# ScreenBoard.net
KiCad netlist of a schematic drawn in Altium Designer
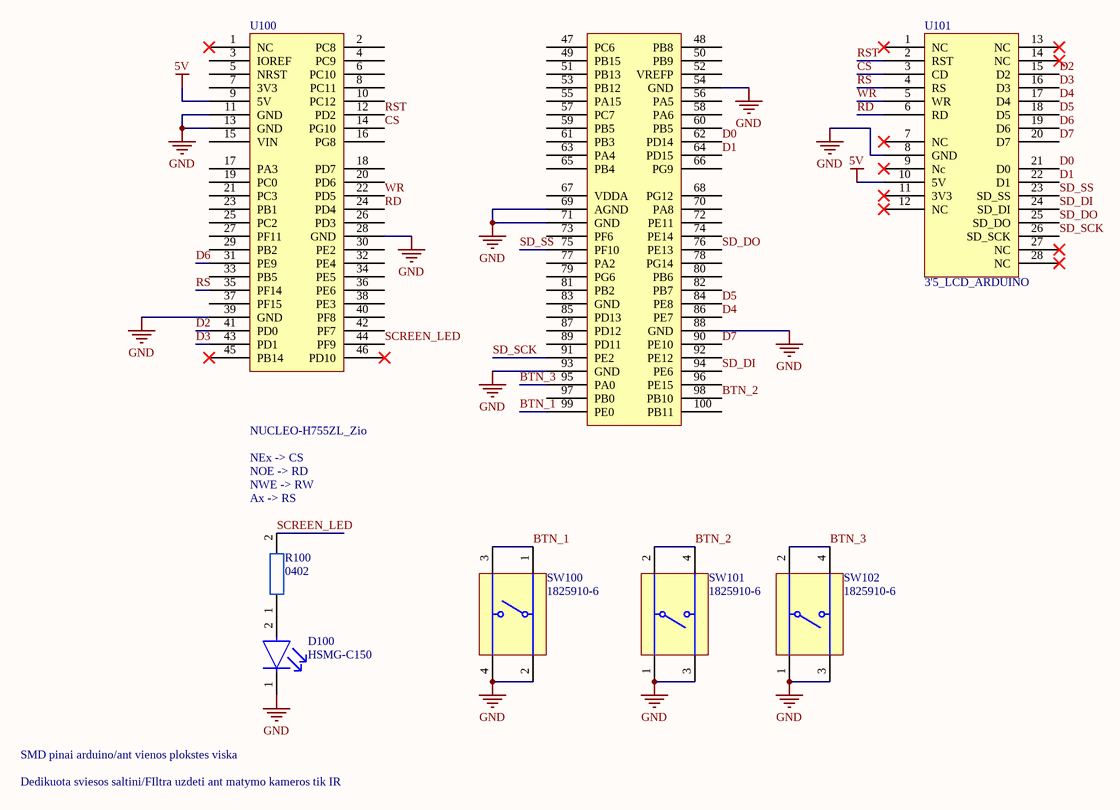
[diagram p0: ScreenBoard.SchDoc]

(export (version "E")
  (design (tool "Eeschema 10.0.6"))
  (components
    (comp (ref "D100")
      (value "HSMG-C150")
      (footprint "FP-HSMG-C150-MFG")
      (description "LED GREEN DIFFUSED 1206 SMD")
      (fields
        (field (name "MANUFACTURER") "Broadcom")
        (field (name "OCTOPART") "https://octopart.com/hsmg-c150-broadcom-71131304")
      )
      (libsource (lib "Altium Content Vault") (part "8706943c75ba83719d021d2fdc84c58"))
    )
    (comp (ref "R100")
      (value "0402")
      (footprint "0402_footprint")
      (description "0402 resistor")
      (libsource (lib "Schlib1") (part "Resistor_0402"))
    )
    (comp (ref "SW100")
      (value "1825910-6")
      (footprint "TECO-1825910-6_V")
      (description "Tact Switch, SPST-NO, 0.05 A, -35 to 85 degC, 4-Pin THD, RoHS, Bulk")
      (fields (field (name "MANUFACTURER") "TE Connectivity"))
      (libsource (lib "") (part "SW-SPST-4_A_1"))
    )
    (comp (ref "SW101")
      (value "1825910-6")
      (footprint "TECO-1825910-6_V")
      (description "Tact Switch, SPST-NO, 0.05 A, -35 to 85 degC, 4-Pin THD, RoHS, Bulk")
      (fields (field (name "MANUFACTURER") "TE Connectivity"))
      (libsource (lib "Altium Content Vault") (part "SW-SPST-4_A"))
    )
    (comp (ref "SW102")
      (value "1825910-6")
      (footprint "TECO-1825910-6_V")
      (description "Tact Switch, SPST-NO, 0.05 A, -35 to 85 degC, 4-Pin THD, RoHS, Bulk")
      (fields (field (name "MANUFACTURER") "TE Connectivity"))
      (libsource (lib "Altium Content Vault") (part "SW-SPST-4_A"))
    )
    (comp (ref "U100")
      (value "NUCLEO-H755ZL_Zio")
      (footprint "H7/H5_NUCLEO_Zio")
      (libsource (lib "Schlib1") (part "NUCLEO-H755ZL_Zio"))
    )
    (comp (ref "U101")
      (value "3'5_LCD_ARDUINO")
      (footprint "3'5_LCD_ARDUINO")
      (libsource (lib "Schlib1") (part "3'5_LCD_ARDUINO"))
    )
  )
  (nets
    (net (code "1") (name "/BTN_1") (class "Default")
      (node (ref "SW100") (pin "1") (pinfunction "1_1") (pintype "passive"))
      (node (ref "SW100") (pin "3") (pinfunction "3_3") (pintype "passive"))
      (node (ref "U100") (pin "99") (pinfunction "PE0_99") (pintype "passive"))
    )
    (net (code "2") (name "/BTN_2") (class "Default")
      (node (ref "SW101") (pin "2") (pinfunction "2_2") (pintype "passive"))
      (node (ref "SW101") (pin "4") (pinfunction "4_4") (pintype "passive"))
      (node (ref "U100") (pin "98") (pinfunction "PB10_98") (pintype "passive"))
    )
    (net (code "3") (name "/BTN_3") (class "Default")
      (node (ref "SW102") (pin "2") (pinfunction "2_2") (pintype "passive"))
      (node (ref "SW102") (pin "4") (pinfunction "4_4") (pintype "passive"))
      (node (ref "U100") (pin "95") (pinfunction "PA0_95") (pintype "passive"))
    )
    (net (code "4") (name "/CS") (class "Default")
      (node (ref "U100") (pin "14") (pinfunction "PG10_14") (pintype "passive"))
      (node (ref "U101") (pin "3") (pinfunction "CD_3") (pintype "passive"))
    )
    (net (code "5") (name "/D0") (class "Default")
      (node (ref "U100") (pin "62") (pinfunction "PD14_62") (pintype "passive"))
      (node (ref "U101") (pin "21") (pinfunction "D0_21") (pintype "passive"))
    )
    (net (code "6") (name "/D1") (class "Default")
      (node (ref "U100") (pin "64") (pinfunction "PD15_64") (pintype "passive"))
      (node (ref "U101") (pin "22") (pinfunction "D1_22") (pintype "passive"))
    )
    (net (code "7") (name "/D2") (class "Default")
      (node (ref "U100") (pin "41") (pinfunction "PD0_41") (pintype "passive"))
      (node (ref "U101") (pin "15") (pinfunction "D2_15") (pintype "passive"))
    )
    (net (code "8") (name "/D3") (class "Default")
      (node (ref "U100") (pin "43") (pinfunction "PD1_43") (pintype "passive"))
      (node (ref "U101") (pin "16") (pinfunction "D3_16") (pintype "passive"))
    )
    (net (code "9") (name "/D4") (class "Default")
      (node (ref "U100") (pin "86") (pinfunction "PE7_86") (pintype "passive"))
      (node (ref "U101") (pin "17") (pinfunction "D4_17") (pintype "passive"))
    )
    (net (code "10") (name "/D5") (class "Default")
      (node (ref "U100") (pin "84") (pinfunction "PE8_84") (pintype "passive"))
      (node (ref "U101") (pin "18") (pinfunction "D5_18") (pintype "passive"))
    )
    (net (code "11") (name "/D6") (class "Default")
      (node (ref "U100") (pin "31") (pinfunction "PE9_31") (pintype "passive"))
      (node (ref "U101") (pin "19") (pinfunction "D6_19") (pintype "passive"))
    )
    (net (code "12") (name "/D7") (class "Default")
      (node (ref "U100") (pin "90") (pinfunction "PE10_90") (pintype "passive"))
      (node (ref "U101") (pin "20") (pinfunction "D7_20") (pintype "passive"))
    )
    (net (code "13") (name "/RD") (class "Default")
      (node (ref "U100") (pin "24") (pinfunction "PD4_24") (pintype "passive"))
      (node (ref "U101") (pin "6") (pinfunction "RD_6") (pintype "passive"))
    )
    (net (code "14") (name "/RS") (class "Default")
      (node (ref "U100") (pin "35") (pinfunction "PF14_35") (pintype "passive"))
      (node (ref "U101") (pin "4") (pinfunction "RS_4") (pintype "passive"))
    )
    (net (code "15") (name "/RST") (class "Default")
      (node (ref "U100") (pin "12") (pinfunction "PD2_12") (pintype "passive"))
      (node (ref "U101") (pin "2") (pinfunction "RST_2") (pintype "passive"))
    )
    (net (code "16") (name "/SCREEN_LED") (class "Default")
      (node (ref "R100") (pin "2") (pinfunction "2_2") (pintype "passive"))
      (node (ref "U100") (pin "44") (pinfunction "PF9_44") (pintype "passive"))
    )
    (net (code "17") (name "/SD_DI") (class "Default")
      (node (ref "U100") (pin "94") (pinfunction "PE6_94") (pintype "passive"))
      (node (ref "U101") (pin "24") (pinfunction "SD_DI_24") (pintype "passive"))
    )
    (net (code "18") (name "/SD_DO") (class "Default")
      (node (ref "U100") (pin "76") (pinfunction "PE13_76") (pintype "passive"))
      (node (ref "U101") (pin "25") (pinfunction "SD_DO_25") (pintype "passive"))
    )
    (net (code "19") (name "/SD_SCK") (class "Default")
      (node (ref "U100") (pin "91") (pinfunction "PE2_91") (pintype "passive"))
      (node (ref "U101") (pin "26") (pinfunction "SD_SCK_26") (pintype "passive"))
    )
    (net (code "20") (name "/SD_SS") (class "Default")
      (node (ref "U100") (pin "75") (pinfunction "PF10_75") (pintype "passive"))
      (node (ref "U101") (pin "23") (pinfunction "SD_SS_23") (pintype "passive"))
    )
    (net (code "21") (name "/WR") (class "Default")
      (node (ref "U100") (pin "22") (pinfunction "PD5_22") (pintype "passive"))
      (node (ref "U101") (pin "5") (pinfunction "WR_5") (pintype "passive"))
    )
    (net (code "22") (name "5V") (class "Default")
      (node (ref "U100") (pin "9") (pinfunction "5V_9") (pintype "passive"))
      (node (ref "U101") (pin "10") (pinfunction "5V_10") (pintype "passive"))
    )
    (net (code "23") (name "GND") (class "Default")
      (node (ref "D100") (pin "1") (pinfunction "C_1") (pintype "passive"))
      (node (ref "SW100") (pin "2") (pinfunction "2_2") (pintype "passive"))
      (node (ref "SW100") (pin "4") (pinfunction "4_4") (pintype "passive"))
      (node (ref "SW101") (pin "1") (pinfunction "1_1") (pintype "passive"))
      (node (ref "SW101") (pin "3") (pinfunction "3_3") (pintype "passive"))
      (node (ref "SW102") (pin "1") (pinfunction "1_1") (pintype "passive"))
      (node (ref "SW102") (pin "3") (pinfunction "3_3") (pintype "passive"))
      (node (ref "U100") (pin "11") (pinfunction "GND_11") (pintype "passive"))
      (node (ref "U100") (pin "13") (pinfunction "GND_13") (pintype "passive"))
      (node (ref "U100") (pin "28") (pinfunction "GND_28") (pintype "passive"))
      (node (ref "U100") (pin "39") (pinfunction "GND_39") (pintype "passive"))
      (node (ref "U100") (pin "54") (pinfunction "GND_54") (pintype "passive"))
      (node (ref "U100") (pin "69") (pinfunction "AGND_69") (pintype "passive"))
      (node (ref "U100") (pin "71") (pinfunction "GND_71") (pintype "passive"))
      (node (ref "U100") (pin "88") (pinfunction "GND_88") (pintype "passive"))
      (node (ref "U100") (pin "93") (pinfunction "GND_93") (pintype "passive"))
      (node (ref "U101") (pin "8") (pinfunction "GND_8") (pintype "passive"))
    )
    (net (code "24") (name "Net-(D100-A)") (class "Default")
      (node (ref "D100") (pin "2") (pinfunction "A_2") (pintype "passive"))
      (node (ref "R100") (pin "1") (pinfunction "1_1") (pintype "passive"))
    )
    (net (code "25") (name "unconnected-(U100-3V3-Pad7)") (class "Default")
      (node (ref "U100") (pin "7") (pinfunction "3V3_7") (pintype "passive"))
    )
    (net (code "26") (name "unconnected-(U100-GND-Pad83)") (class "Default")
      (node (ref "U100") (pin "83") (pinfunction "GND_83") (pintype "passive"))
    )
    (net (code "27") (name "unconnected-(U100-IOREF-Pad3)") (class "Default")
      (node (ref "U100") (pin "3") (pinfunction "IOREF_3") (pintype "passive"))
    )
    (net (code "28") (name "unconnected-(U100-NC-Pad1)") (class "Default")
      (node (ref "U100") (pin "1") (pinfunction "NC_1") (pintype "passive+no_connect"))
    )
    (net (code "29") (name "unconnected-(U100-NRST-Pad5)") (class "Default")
      (node (ref "U100") (pin "5") (pinfunction "NRST_5") (pintype "passive"))
    )
    (net (code "30") (name "unconnected-(U100-PA2-Pad77)") (class "Default")
      (node (ref "U100") (pin "77") (pinfunction "PA2_77") (pintype "passive"))
    )
    (net (code "31") (name "unconnected-(U100-PA3-Pad17)") (class "Default")
      (node (ref "U100") (pin "17") (pinfunction "PA3_17") (pintype "passive"))
    )
    (net (code "32") (name "unconnected-(U100-PA4-Pad63)") (class "Default")
      (node (ref "U100") (pin "63") (pinfunction "PA4_63") (pintype "passive"))
    )
    (net (code "33") (name "unconnected-(U100-PA5-Pad56)") (class "Default")
      (node (ref "U100") (pin "56") (pinfunction "PA5_56") (pintype "passive"))
    )
    (net (code "34") (name "unconnected-(U100-PA6-Pad58)") (class "Default")
      (node (ref "U100") (pin "58") (pinfunction "PA6_58") (pintype "passive"))
    )
    (net (code "35") (name "unconnected-(U100-PA8-Pad70)") (class "Default")
      (node (ref "U100") (pin "70") (pinfunction "PA8_70") (pintype "passive"))
    )
    (net (code "36") (name "unconnected-(U100-PA15-Pad55)") (class "Default")
      (node (ref "U100") (pin "55") (pinfunction "PA15_55") (pintype "passive"))
    )
    (net (code "37") (name "unconnected-(U100-PB0-Pad97)") (class "Default")
      (node (ref "U100") (pin "97") (pinfunction "PB0_97") (pintype "passive"))
    )
    (net (code "38") (name "unconnected-(U100-PB1-Pad23)") (class "Default")
      (node (ref "U100") (pin "23") (pinfunction "PB1_23") (pintype "passive"))
    )
    (net (code "39") (name "unconnected-(U100-PB2-Pad29)") (class "Default")
      (node (ref "U100") (pin "29") (pinfunction "PB2_29") (pintype "passive"))
    )
    (net (code "40") (name "unconnected-(U100-PB2-Pad81)") (class "Default")
      (node (ref "U100") (pin "81") (pinfunction "PB2_81") (pintype "passive"))
    )
    (net (code "41") (name "unconnected-(U100-PB3-Pad61)") (class "Default")
      (node (ref "U100") (pin "61") (pinfunction "PB3_61") (pintype "passive"))
    )
    (net (code "42") (name "unconnected-(U100-PB4-Pad65)") (class "Default")
      (node (ref "U100") (pin "65") (pinfunction "PB4_65") (pintype "passive"))
    )
    (net (code "43") (name "unconnected-(U100-PB5-Pad33)") (class "Default")
      (node (ref "U100") (pin "33") (pinfunction "PB5_33") (pintype "passive"))
    )
    (net (code "44") (name "unconnected-(U100-PB5-Pad59)") (class "Default")
      (node (ref "U100") (pin "59") (pinfunction "PB5_59") (pintype "passive"))
    )
    (net (code "45") (name "unconnected-(U100-PB5-Pad60)") (class "Default")
      (node (ref "U100") (pin "60") (pinfunction "PB5_60") (pintype "passive"))
    )
    (net (code "46") (name "unconnected-(U100-PB6-Pad80)") (class "Default")
      (node (ref "U100") (pin "80") (pinfunction "PB6_80") (pintype "passive"))
    )
    (net (code "47") (name "unconnected-(U100-PB7-Pad82)") (class "Default")
      (node (ref "U100") (pin "82") (pinfunction "PB7_82") (pintype "passive"))
    )
    (net (code "48") (name "unconnected-(U100-PB8-Pad48)") (class "Default")
      (node (ref "U100") (pin "48") (pinfunction "PB8_48") (pintype "passive"))
    )
    (net (code "49") (name "unconnected-(U100-PB9-Pad50)") (class "Default")
      (node (ref "U100") (pin "50") (pinfunction "PB9_50") (pintype "passive"))
    )
    (net (code "50") (name "unconnected-(U100-PB11-Pad100)") (class "Default")
      (node (ref "U100") (pin "100") (pinfunction "PB11_100") (pintype "passive"))
    )
    (net (code "51") (name "unconnected-(U100-PB12-Pad53)") (class "Default")
      (node (ref "U100") (pin "53") (pinfunction "PB12_53") (pintype "passive"))
    )
    (net (code "52") (name "unconnected-(U100-PB13-Pad51)") (class "Default")
      (node (ref "U100") (pin "51") (pinfunction "PB13_51") (pintype "passive"))
    )
    (net (code "53") (name "unconnected-(U100-PB14-Pad45)") (class "Default")
      (node (ref "U100") (pin "45") (pinfunction "PB14_45") (pintype "passive+no_connect"))
    )
    (net (code "54") (name "unconnected-(U100-PB15-Pad49)") (class "Default")
      (node (ref "U100") (pin "49") (pinfunction "PB15_49") (pintype "passive"))
    )
    (net (code "55") (name "unconnected-(U100-PC0-Pad19)") (class "Default")
      (node (ref "U100") (pin "19") (pinfunction "PC0_19") (pintype "passive"))
    )
    (net (code "56") (name "unconnected-(U100-PC2-Pad25)") (class "Default")
      (node (ref "U100") (pin "25") (pinfunction "PC2_25") (pintype "passive"))
    )
    (net (code "57") (name "unconnected-(U100-PC3-Pad21)") (class "Default")
      (node (ref "U100") (pin "21") (pinfunction "PC3_21") (pintype "passive"))
    )
    (net (code "58") (name "unconnected-(U100-PC6-Pad47)") (class "Default")
      (node (ref "U100") (pin "47") (pinfunction "PC6_47") (pintype "passive"))
    )
    (net (code "59") (name "unconnected-(U100-PC7-Pad57)") (class "Default")
      (node (ref "U100") (pin "57") (pinfunction "PC7_57") (pintype "passive"))
    )
    (net (code "60") (name "unconnected-(U100-PC8-Pad2)") (class "Default")
      (node (ref "U100") (pin "2") (pinfunction "PC8_2") (pintype "passive"))
    )
    (net (code "61") (name "unconnected-(U100-PC9-Pad4)") (class "Default")
      (node (ref "U100") (pin "4") (pinfunction "PC9_4") (pintype "passive"))
    )
    (net (code "62") (name "unconnected-(U100-PC10-Pad6)") (class "Default")
      (node (ref "U100") (pin "6") (pinfunction "PC10_6") (pintype "passive"))
    )
    (net (code "63") (name "unconnected-(U100-PC11-Pad8)") (class "Default")
      (node (ref "U100") (pin "8") (pinfunction "PC11_8") (pintype "passive"))
    )
    (net (code "64") (name "unconnected-(U100-PC12-Pad10)") (class "Default")
      (node (ref "U100") (pin "10") (pinfunction "PC12_10") (pintype "passive"))
    )
    (net (code "65") (name "unconnected-(U100-PD3-Pad26)") (class "Default")
      (node (ref "U100") (pin "26") (pinfunction "PD3_26") (pintype "passive"))
    )
    (net (code "66") (name "unconnected-(U100-PD6-Pad20)") (class "Default")
      (node (ref "U100") (pin "20") (pinfunction "PD6_20") (pintype "passive"))
    )
    (net (code "67") (name "unconnected-(U100-PD7-Pad18)") (class "Default")
      (node (ref "U100") (pin "18") (pinfunction "PD7_18") (pintype "passive"))
    )
    (net (code "68") (name "unconnected-(U100-PD10-Pad46)") (class "Default")
      (node (ref "U100") (pin "46") (pinfunction "PD10_46") (pintype "passive+no_connect"))
    )
    (net (code "69") (name "unconnected-(U100-PD11-Pad89)") (class "Default")
      (node (ref "U100") (pin "89") (pinfunction "PD11_89") (pintype "passive"))
    )
    (net (code "70") (name "unconnected-(U100-PD12-Pad87)") (class "Default")
      (node (ref "U100") (pin "87") (pinfunction "PD12_87") (pintype "passive"))
    )
    (net (code "71") (name "unconnected-(U100-PD13-Pad85)") (class "Default")
      (node (ref "U100") (pin "85") (pinfunction "PD13_85") (pintype "passive"))
    )
    (net (code "72") (name "unconnected-(U100-PE2-Pad30)") (class "Default")
      (node (ref "U100") (pin "30") (pinfunction "PE2_30") (pintype "passive"))
    )
    (net (code "73") (name "unconnected-(U100-PE3-Pad38)") (class "Default")
      (node (ref "U100") (pin "38") (pinfunction "PE3_38") (pintype "passive"))
    )
    (net (code "74") (name "unconnected-(U100-PE4-Pad32)") (class "Default")
      (node (ref "U100") (pin "32") (pinfunction "PE4_32") (pintype "passive"))
    )
    (net (code "75") (name "unconnected-(U100-PE5-Pad34)") (class "Default")
      (node (ref "U100") (pin "34") (pinfunction "PE5_34") (pintype "passive"))
    )
    (net (code "76") (name "unconnected-(U100-PE6-Pad36)") (class "Default")
      (node (ref "U100") (pin "36") (pinfunction "PE6_36") (pintype "passive"))
    )
    (net (code "77") (name "unconnected-(U100-PE11-Pad72)") (class "Default")
      (node (ref "U100") (pin "72") (pinfunction "PE11_72") (pintype "passive"))
    )
    (net (code "78") (name "unconnected-(U100-PE12-Pad92)") (class "Default")
      (node (ref "U100") (pin "92") (pinfunction "PE12_92") (pintype "passive"))
    )
    (net (code "79") (name "unconnected-(U100-PE14-Pad74)") (class "Default")
      (node (ref "U100") (pin "74") (pinfunction "PE14_74") (pintype "passive"))
    )
    (net (code "80") (name "unconnected-(U100-PE15-Pad96)") (class "Default")
      (node (ref "U100") (pin "96") (pinfunction "PE15_96") (pintype "passive"))
    )
    (net (code "81") (name "unconnected-(U100-PF6-Pad73)") (class "Default")
      (node (ref "U100") (pin "73") (pinfunction "PF6_73") (pintype "passive"))
    )
    (net (code "82") (name "unconnected-(U100-PF7-Pad42)") (class "Default")
      (node (ref "U100") (pin "42") (pinfunction "PF7_42") (pintype "passive"))
    )
    (net (code "83") (name "unconnected-(U100-PF8-Pad40)") (class "Default")
      (node (ref "U100") (pin "40") (pinfunction "PF8_40") (pintype "passive"))
    )
    (net (code "84") (name "unconnected-(U100-PF11-Pad27)") (class "Default")
      (node (ref "U100") (pin "27") (pinfunction "PF11_27") (pintype "passive"))
    )
    (net (code "85") (name "unconnected-(U100-PF15-Pad37)") (class "Default")
      (node (ref "U100") (pin "37") (pinfunction "PF15_37") (pintype "passive"))
    )
    (net (code "86") (name "unconnected-(U100-PG6-Pad79)") (class "Default")
      (node (ref "U100") (pin "79") (pinfunction "PG6_79") (pintype "passive"))
    )
    (net (code "87") (name "unconnected-(U100-PG8-Pad16)") (class "Default")
      (node (ref "U100") (pin "16") (pinfunction "PG8_16") (pintype "passive"))
    )
    (net (code "88") (name "unconnected-(U100-PG9-Pad66)") (class "Default")
      (node (ref "U100") (pin "66") (pinfunction "PG9_66") (pintype "passive"))
    )
    (net (code "89") (name "unconnected-(U100-PG12-Pad68)") (class "Default")
      (node (ref "U100") (pin "68") (pinfunction "PG12_68") (pintype "passive"))
    )
    (net (code "90") (name "unconnected-(U100-PG14-Pad78)") (class "Default")
      (node (ref "U100") (pin "78") (pinfunction "PG14_78") (pintype "passive"))
    )
    (net (code "91") (name "unconnected-(U100-VDDA-Pad67)") (class "Default")
      (node (ref "U100") (pin "67") (pinfunction "VDDA_67") (pintype "passive"))
    )
    (net (code "92") (name "unconnected-(U100-VIN-Pad15)") (class "Default")
      (node (ref "U100") (pin "15") (pinfunction "VIN_15") (pintype "passive"))
    )
    (net (code "93") (name "unconnected-(U100-VREFP-Pad52)") (class "Default")
      (node (ref "U100") (pin "52") (pinfunction "VREFP_52") (pintype "passive"))
    )
    (net (code "94") (name "unconnected-(U101-3V3-Pad11)") (class "Default")
      (node (ref "U101") (pin "11") (pinfunction "3V3_11") (pintype "passive+no_connect"))
    )
    (net (code "95") (name "unconnected-(U101-NC-Pad1)") (class "Default")
      (node (ref "U101") (pin "1") (pinfunction "NC_1") (pintype "passive+no_connect"))
    )
    (net (code "96") (name "unconnected-(U101-NC-Pad7)") (class "Default")
      (node (ref "U101") (pin "7") (pinfunction "NC_7") (pintype "passive+no_connect"))
    )
    (net (code "97") (name "unconnected-(U101-NC-Pad12)") (class "Default")
      (node (ref "U101") (pin "12") (pinfunction "NC_12") (pintype "passive+no_connect"))
    )
    (net (code "98") (name "unconnected-(U101-NC-Pad13)") (class "Default")
      (node (ref "U101") (pin "13") (pinfunction "NC_13") (pintype "passive+no_connect"))
    )
    (net (code "99") (name "unconnected-(U101-NC-Pad14)") (class "Default")
      (node (ref "U101") (pin "14") (pinfunction "NC_14") (pintype "passive+no_connect"))
    )
    (net (code "100") (name "unconnected-(U101-NC-Pad27)") (class "Default")
      (node (ref "U101") (pin "27") (pinfunction "NC_27") (pintype "passive+no_connect"))
    )
    (net (code "101") (name "unconnected-(U101-NC-Pad28)") (class "Default")
      (node (ref "U101") (pin "28") (pinfunction "NC_28") (pintype "passive+no_connect"))
    )
    (net (code "102") (name "unconnected-(U101-Nc-Pad9)") (class "Default")
      (node (ref "U101") (pin "9") (pinfunction "Nc_9") (pintype "passive+no_connect"))
    )
  )
)
